# Microfono.net
KiCad netlist of a schematic drawn in Altium Designer
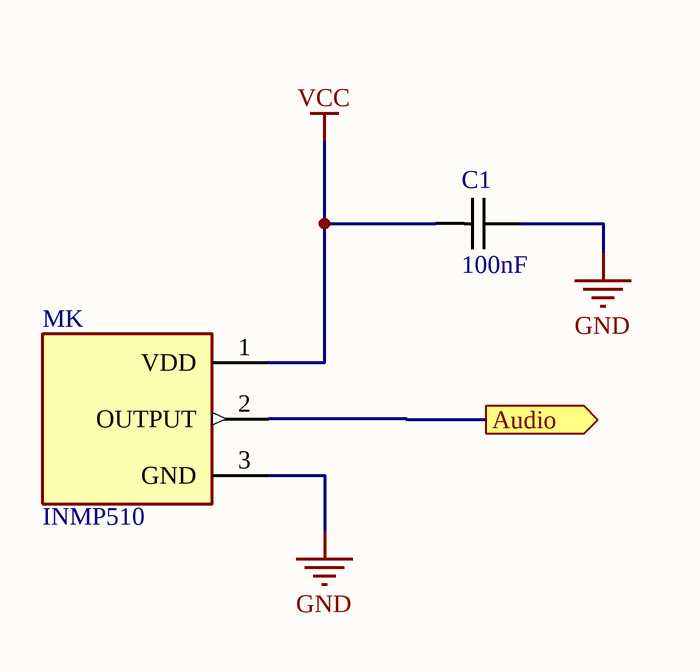
[diagram p0: Microfono.SchDoc]

(export (version "E")
  (design (tool "Eeschema 10.0.6"))
  (components
    (comp (ref "C1")
      (value "100nF")
      (footprint "0805C-TBD")
      (description "CAPACITOR 0805 CERAMIC")
      (libsource (lib "vh_altium_library") (part "0805C-100nF-25V-X7R-MUR"))
    )
    (comp (ref "MK")
      (value "INMP510")
      (footprint "XDCR_INMP510")
      (fields (field (name "DIGI-KEY_PART_NUMBER") "1428-1016-2-ND") (field (name "MF") "TDK InvenSense"))
      (libsource (lib "INMP510") (part "INMP510"))
    )
  )
  (nets
    (net (code "1") (name "/Audio") (class "Default")
      (node (ref "MK") (pin "2") (pinfunction "OUTPUT_2") (pintype "output"))
    )
    (net (code "2") (name "GND") (class "Default")
      (node (ref "C1") (pin "2") (pintype "passive"))
      (node (ref "MK") (pin "3") (pinfunction "GND_3") (pintype "power_in"))
    )
    (net (code "3") (name "VCC") (class "Default")
      (node (ref "C1") (pin "1") (pintype "passive"))
      (node (ref "MK") (pin "1") (pinfunction "VDD_1") (pintype "power_in"))
    )
  )
)
